# Driver_Morpheus_PONTE_H.net
KiCad netlist of a schematic drawn in Altium Designer
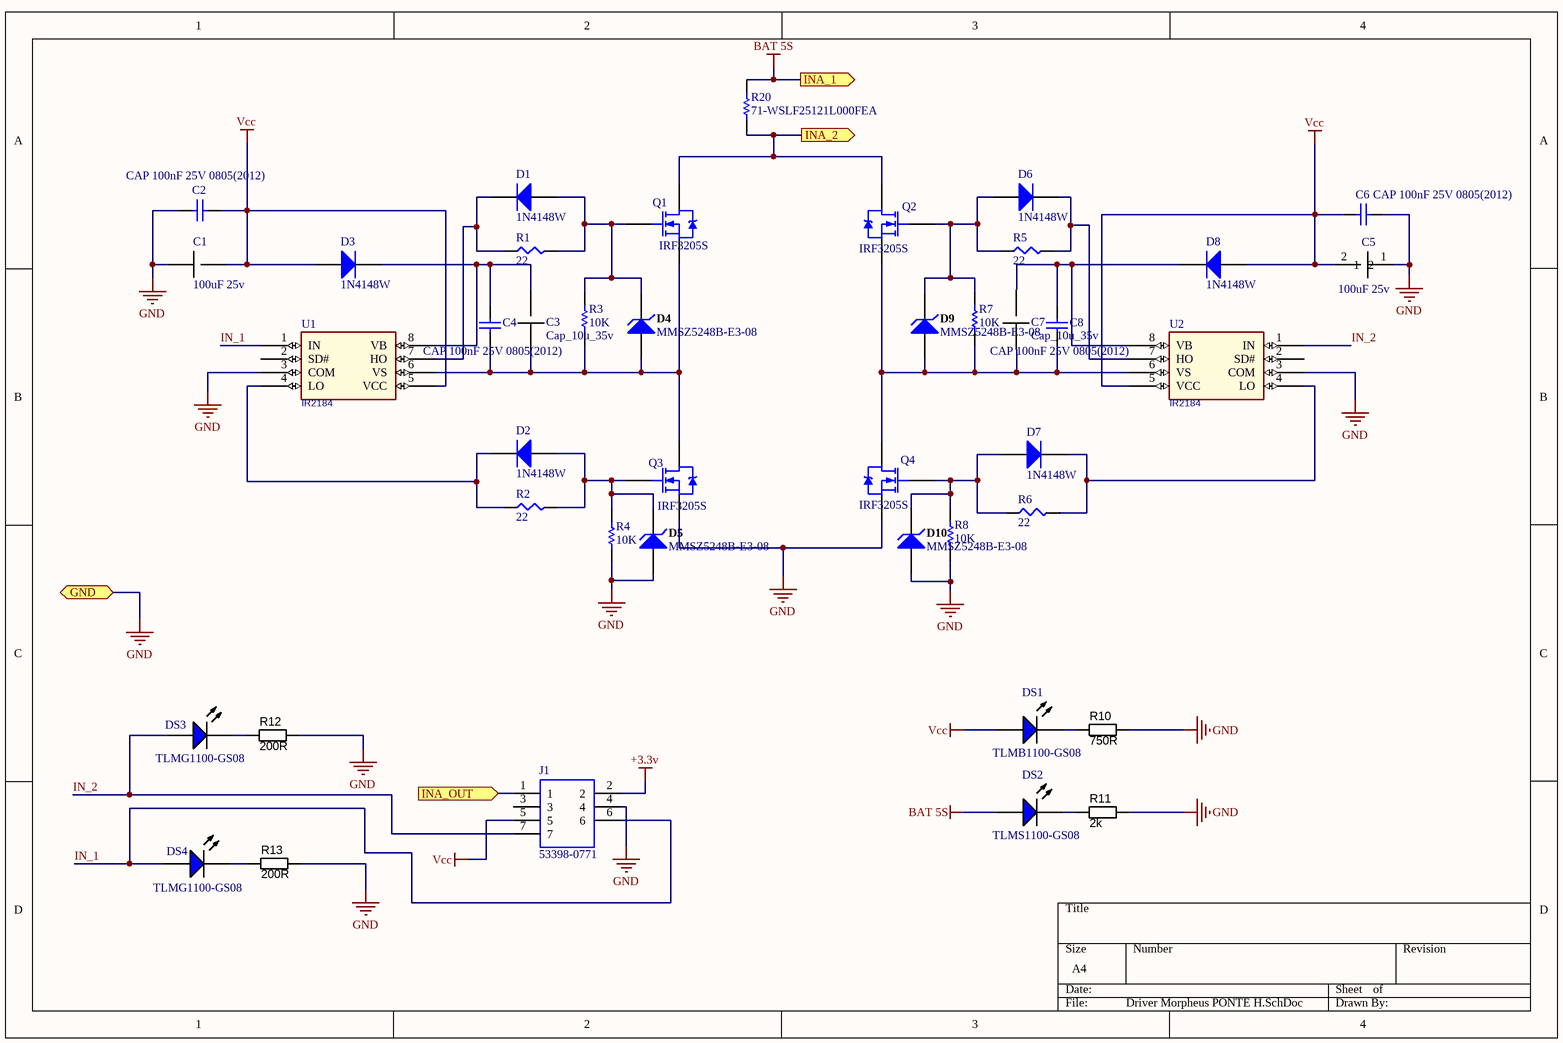
[diagram p0: Driver Morpheus PONTE H.SchDoc]

(export (version "E")
  (design (tool "Eeschema 10.0.6"))
  (components
    (comp (ref "C1")
      (value "100uF 25v")
      (footprint "CAPAE9083X70M")
      (libsource (lib "LibSanhaço2017") (part "Cap_10u_35v"))
    )
    (comp (ref "C2")
      (value "CAP 100nF 25V 0805(2012)")
      (footprint "CAPC0805(2012)145_M")
      (description "CAP 100nF 25V ±5% 0805 (2012 Metric) Thickness 1.45mm SMD")
      (fields (field (name "TOLERANCE") "Â±5%"))
      (libsource (lib "Altium Content Vault") (part "CAP"))
    )
    (comp (ref "C3")
      (value "Cap_10u_35v")
      (footprint "CAP POL 2917/7343")
      (libsource (lib "LibSanhaço2017") (part "Cap_10u_35v"))
    )
    (comp (ref "C4")
      (value "CAP 100nF 25V 0805(2012)")
      (footprint "CAPC0805(2012)145_M")
      (description "CAP 100nF 25V ±5% 0805 (2012 Metric) Thickness 1.45mm SMD")
      (fields (field (name "TOLERANCE") "Â±5%"))
      (libsource (lib "Altium Content Vault") (part "CAP"))
    )
    (comp (ref "C5")
      (value "100uF 25v")
      (footprint "CAPAE9083X70M")
      (description "Cap Tântalo")
      (libsource (lib "LibSanhaço2017") (part "Cap_100u_25v"))
    )
    (comp (ref "C6")
      (value "CAP 100nF 25V 0805(2012)")
      (footprint "CAPC0805(2012)145_M")
      (description "CAP 100nF 25V ±5% 0805 (2012 Metric) Thickness 1.45mm SMD")
      (fields (field (name "TOLERANCE") "Â±5%"))
      (libsource (lib "Altium Content Vault") (part "CAP"))
    )
    (comp (ref "C7")
      (value "Cap_10u_35v")
      (footprint "CAP POL 2917/7343")
      (libsource (lib "LibSanhaço2017") (part "Cap_10u_35v"))
    )
    (comp (ref "C8")
      (value "CAP 100nF 25V 0805(2012)")
      (footprint "CAPC0805(2012)145_M")
      (description "CAP 100nF 25V ±5% 0805 (2012 Metric) Thickness 1.45mm SMD")
      (fields (field (name "TOLERANCE") "Â±5%"))
      (libsource (lib "Altium Content Vault") (part "CAP"))
    )
    (comp (ref "D1")
      (value "1N4148W")
      (footprint "JSCJ-SOD-123-2_V")
      (description "Fast Switching Diode, 75 V, 150 mA, 2-Pin 2.7 x 1.6 x 1.25 mm SMD, Tape and Reel")
      (fields (field (name "MANUFACTURER") "Changjiang Electronics"))
      (libsource (lib "Altium Content Vault") (part "JSCJ-A1K2-2"))
    )
    (comp (ref "D2")
      (value "1N4148W")
      (footprint "JSCJ-SOD-123-2_V")
      (description "Fast Switching Diode, 75 V, 150 mA, 2-Pin 2.7 x 1.6 x 1.25 mm SMD, Tape and Reel")
      (fields (field (name "MANUFACTURER") "Changjiang Electronics"))
      (libsource (lib "Altium Content Vault") (part "JSCJ-A1K2-2"))
    )
    (comp (ref "D3")
      (value "1N4148W")
      (footprint "JSCJ-SOD-123-2_V")
      (description "Fast Switching Diode, 75 V, 150 mA, 2-Pin 2.7 x 1.6 x 1.25 mm SMD, Tape and Reel")
      (fields (field (name "MANUFACTURER") "Changjiang Electronics"))
      (libsource (lib "Altium Content Vault") (part "JSCJ-A1K2-2"))
    )
    (comp (ref "D4")
      (value "MMSZ5248B-E3-08")
      (footprint "VISH-SOD-123-2_V")
      (description "Small Signal Zener Diode, 18 V +/- 5%, -55 to 155 degC, 2-Pin SOD-123, RoHS, Tape and Reel")
      (fields (field (name "TOLERANCE") "+/- 5%") (field (name "MANUFACTURER") "Vishay Semiconductor"))
      (libsource (lib "Altium Content Vault") (part "VISH-DZEN_A1K2-2"))
    )
    (comp (ref "D5")
      (value "MMSZ5248B-E3-08")
      (footprint "VISH-SOD-123-2_V")
      (description "Small Signal Zener Diode, 18 V +/- 5%, -55 to 155 degC, 2-Pin SOD-123, RoHS, Tape and Reel")
      (fields (field (name "TOLERANCE") "+/- 5%") (field (name "MANUFACTURER") "Vishay Semiconductor"))
      (libsource (lib "Altium Content Vault") (part "VISH-DZEN_A1K2-2"))
    )
    (comp (ref "D6")
      (value "1N4148W")
      (footprint "JSCJ-SOD-123-2_V")
      (description "Fast Switching Diode, 75 V, 150 mA, 2-Pin 2.7 x 1.6 x 1.25 mm SMD, Tape and Reel")
      (fields (field (name "MANUFACTURER") "Changjiang Electronics"))
      (libsource (lib "Altium Content Vault") (part "JSCJ-A1K2-2"))
    )
    (comp (ref "D7")
      (value "1N4148W")
      (footprint "JSCJ-SOD-123-2_V")
      (description "Fast Switching Diode, 75 V, 150 mA, 2-Pin 2.7 x 1.6 x 1.25 mm SMD, Tape and Reel")
      (fields (field (name "MANUFACTURER") "Changjiang Electronics"))
      (libsource (lib "Altium Content Vault") (part "JSCJ-A1K2-2"))
    )
    (comp (ref "D8")
      (value "1N4148W")
      (footprint "JSCJ-SOD-123-2_V")
      (description "Fast Switching Diode, 75 V, 150 mA, 2-Pin 2.7 x 1.6 x 1.25 mm SMD, Tape and Reel")
      (fields (field (name "MANUFACTURER") "Changjiang Electronics"))
      (libsource (lib "Altium Content Vault") (part "JSCJ-A1K2-2"))
    )
    (comp (ref "D9")
      (value "MMSZ5248B-E3-08")
      (footprint "VISH-SOD-123-2_V")
      (description "Small Signal Zener Diode, 18 V +/- 5%, -55 to 155 degC, 2-Pin SOD-123, RoHS, Tape and Reel")
      (fields (field (name "TOLERANCE") "+/- 5%") (field (name "MANUFACTURER") "Vishay Semiconductor"))
      (libsource (lib "Altium Content Vault") (part "VISH-DZEN_A1K2-2"))
    )
    (comp (ref "D10")
      (value "MMSZ5248B-E3-08")
      (footprint "VISH-SOD-123-2_V")
      (description "Small Signal Zener Diode, 18 V +/- 5%, -55 to 155 degC, 2-Pin SOD-123, RoHS, Tape and Reel")
      (fields (field (name "TOLERANCE") "+/- 5%") (field (name "MANUFACTURER") "Vishay Semiconductor"))
      (libsource (lib "Altium Content Vault") (part "VISH-DZEN_A1K2-2"))
    )
    (comp (ref "DS1")
      (value "TLMB1100-GS08")
      (footprint "VISH-TLMX1100-2_V")
      (fields (field (name "TOLERANCE") "10%"))
      (libsource (lib "Altium Content Vault") (part "LED-BLUE-AK-2"))
    )
    (comp (ref "DS2")
      (value "TLMS1100-GS08")
      (footprint "VISH-TLMX1100-2_V")
      (fields (field (name "TOLERANCE") "10%"))
      (libsource (lib "Altium Content Vault") (part "LED-BLUE-AK-2"))
    )
    (comp (ref "DS3")
      (value "TLMG1100-GS08")
      (footprint "VISH-TLMX1100-2_V")
      (fields (field (name "TOLERANCE") "10%"))
      (libsource (lib "Altium Content Vault") (part "LED-BLUE-AK-2"))
    )
    (comp (ref "DS4")
      (value "TLMG1100-GS08")
      (footprint "VISH-TLMX1100-2_V")
      (fields (field (name "TOLERANCE") "10%"))
      (libsource (lib "Altium Content Vault") (part "LED-BLUE-AK-2"))
    )
    (comp (ref "J1")
      (value "53398-0771")
      (footprint "53398-0771")
      (fields (field (name "RS PART NUMBER") "5427220P"))
      (libsource (lib "53398-0771") (part "53398-0771"))
    )
    (comp (ref "Q1")
      (value "IRF3205S")
      (footprint "D2PAK_N")
      (description "HEXFET Power MOSFET")
      (fields (field (name "PUBLISHER") "Altium Limited"))
      (libsource (lib "IR Discrete MOSFET - Power") (part "IRF3205S"))
    )
    (comp (ref "Q2")
      (value "IRF3205S")
      (footprint "D2PAK_N")
      (description "HEXFET Power MOSFET")
      (fields (field (name "PUBLISHER") "Altium Limited"))
      (libsource (lib "IR Discrete MOSFET - Power") (part "IRF3205S"))
    )
    (comp (ref "Q3")
      (value "IRF3205S")
      (footprint "D2PAK_N")
      (description "HEXFET Power MOSFET")
      (fields (field (name "PUBLISHER") "Altium Limited"))
      (libsource (lib "IR Discrete MOSFET - Power") (part "IRF3205S"))
    )
    (comp (ref "Q4")
      (value "IRF3205S")
      (footprint "D2PAK_N")
      (description "HEXFET Power MOSFET")
      (fields (field (name "PUBLISHER") "Altium Limited"))
      (libsource (lib "IR Discrete MOSFET - Power") (part "IRF3205S"))
    )
    (comp (ref "R1")
      (value "22")
      (footprint "SMD-0603-RES")
      (description "RES SMD 22 OHM 1% 1/10W 0603")
      (fields
        (field (name "PART NUMBER") "ERJ-3EKF22R0V")
        (field (name "DIGI-KEY PART NUMBER") "P22.0HCT-ND")
      )
      (libsource (lib "Panasonic_ERJ_0603") (part "ERJ-3EKF22R0V"))
    )
    (comp (ref "R2")
      (value "22")
      (footprint "SMD-0603-RES")
      (description "RES SMD 22 OHM 1% 1/10W 0603")
      (fields
        (field (name "PART NUMBER") "ERJ-3EKF22R0V")
        (field (name "DIGI-KEY PART NUMBER") "P22.0HCT-ND")
      )
      (libsource (lib "Panasonic_ERJ_0603") (part "ERJ-3EKF22R0V"))
    )
    (comp (ref "R3")
      (value "10K")
      (footprint "RES-0402")
      (description "RES SMD 10K OHM 5% 1/16W 0402")
      (fields (field (name "Comment") "RC0402JR-071KL"))
      (libsource (lib "Schlib1") (part "RES 1K 0402"))
    )
    (comp (ref "R4")
      (value "10K")
      (footprint "RES-0402")
      (description "RES SMD 10K OHM 5% 1/16W 0402")
      (fields (field (name "Comment") "RC0402JR-071KL"))
      (libsource (lib "Schlib1") (part "RES 1K 0402"))
    )
    (comp (ref "R5")
      (value "22")
      (footprint "SMD-0603-RES")
      (description "RES SMD 22 OHM 1% 1/10W 0603")
      (fields
        (field (name "PART NUMBER") "ERJ-3EKF22R0V")
        (field (name "DIGI-KEY PART NUMBER") "P22.0HCT-ND")
      )
      (libsource (lib "Panasonic_ERJ_0603") (part "ERJ-3EKF22R0V"))
    )
    (comp (ref "R6")
      (value "22")
      (footprint "SMD-0603-RES")
      (description "RES SMD 22 OHM 1% 1/10W 0603")
      (fields
        (field (name "PART NUMBER") "ERJ-3EKF22R0V")
        (field (name "DIGI-KEY PART NUMBER") "P22.0HCT-ND")
      )
      (libsource (lib "Panasonic_ERJ_0603") (part "ERJ-3EKF22R0V"))
    )
    (comp (ref "R7")
      (value "10K")
      (footprint "RES-0402")
      (description "RES SMD 10K OHM 5% 1/16W 0402")
      (fields (field (name "Comment") "RC0402JR-071KL"))
      (libsource (lib "Schlib1") (part "RES 1K 0402"))
    )
    (comp (ref "R8")
      (value "10K")
      (footprint "RES-0402")
      (description "RES SMD 10K OHM 5% 1/16W 0402")
      (fields (field (name "Comment") "RC0402JR-071KL"))
      (libsource (lib "Schlib1") (part "RES 1K 0402"))
    )
    (comp (ref "R10")
      (value "750R")
      (footprint "RESC1608X55N")
      (description "Resistor SMD chip 750 Ohm 1/16W 5% 0603")
      (fields (field (name "TOLERANCE") "±5%") (field (name "Comment") "Thick Film"))
      (libsource (lib "PBL - Resistors") (part "RES_220R_0603_5%"))
    )
    (comp (ref "R11")
      (value "2k")
      (footprint "RESC1608X55N")
      (description "Resistor SMD chip 2k Ohm 1/16W 5% 0603")
      (fields (field (name "TOLERANCE") "±5%") (field (name "Comment") "Thick Film"))
      (libsource (lib "PBL - Resistors") (part "RES_220R_0603_5%"))
    )
    (comp (ref "R12")
      (value "200R")
      (footprint "RESC1608X55N")
      (description "Resistor SMD chip 200 Ohm 1/16W 5% 0603")
      (fields (field (name "TOLERANCE") "±5%") (field (name "Comment") "Thick Film"))
      (libsource (lib "PBL - Resistors") (part "RES_220R_0603_5%"))
    )
    (comp (ref "R13")
      (value "200R")
      (footprint "RESC1608X55N")
      (description "Resistor SMD chip 200 Ohm 1/16W 5% 0603")
      (fields (field (name "TOLERANCE") "±5%") (field (name "Comment") "Thick Film"))
      (libsource (lib "PBL - Resistors") (part "RES_220R_0603_5%"))
    )
    (comp (ref "R20")
      (value "71-WSLF25121L000FEA")
      (footprint "RESC6432X89X76ML25T25")
      (fields (field (name "MANUFACTURER") "Vishay") (field (name "TOLERANCE") "1%"))
      (libsource (lib "Resistor 2512 1m") (part "CMP-2000-07419-1"))
    )
    (comp (ref "U1") (value "IR2184") (libsource (lib "") (part "IR2184_1")))
    (comp (ref "U2") (value "IR2184") (libsource (lib "IR2184_Library") (part "IR2184")))
  )
  (nets
    (net (code "1") (name "+3.3v") (class "Default")
      (node (ref "J1") (pin "2") (pinfunction "2_2") (pintype "passive"))
    )
    (net (code "2") (name "/INA_2") (class "Default")
      (node (ref "Q1") (pin "2") (pinfunction "D_2") (pintype "passive"))
      (node (ref "Q2") (pin "2") (pinfunction "D_2") (pintype "passive"))
      (node (ref "R20") (pin "1") (pinfunction "1_1") (pintype "passive"))
    )
    (net (code "3") (name "/INA_OUT") (class "Default")
      (node (ref "J1") (pin "1") (pinfunction "1_1") (pintype "passive"))
    )
    (net (code "4") (name "/IN_1") (class "Default")
      (node (ref "DS4") (pin "1") (pinfunction "A_1") (pintype "passive"))
      (node (ref "J1") (pin "6") (pinfunction "6_6") (pintype "passive"))
      (node (ref "U1") (pin "1") (pinfunction "IN_1") (pintype "bidirectional"))
    )
    (net (code "5") (name "/IN_2") (class "Default")
      (node (ref "DS3") (pin "1") (pinfunction "A_1") (pintype "passive"))
      (node (ref "J1") (pin "7") (pinfunction "7_7") (pintype "passive"))
      (node (ref "U2") (pin "1") (pinfunction "IN_1") (pintype "bidirectional"))
    )
    (net (code "6") (name "BAT 5S") (class "Default")
      (node (ref "DS2") (pin "1") (pinfunction "A_1") (pintype "passive"))
      (node (ref "R20") (pin "2") (pinfunction "2_2") (pintype "passive"))
    )
    (net (code "7") (name "GND") (class "Default")
      (node (ref "C1") (pin "1") (pinfunction "1_1") (pintype "passive"))
      (node (ref "C2") (pin "1") (pinfunction "1_1") (pintype "passive"))
      (node (ref "C5") (pin "1") (pinfunction "1_1") (pintype "passive"))
      (node (ref "C6") (pin "1") (pinfunction "1_1") (pintype "passive"))
      (node (ref "D10") (pin "1") (pinfunction "A_1") (pintype "passive"))
      (node (ref "D5") (pin "1") (pinfunction "A_1") (pintype "passive"))
      (node (ref "J1") (pin "4") (pinfunction "4_4") (pintype "passive"))
      (node (ref "Q3") (pin "3") (pinfunction "S_3") (pintype "passive"))
      (node (ref "Q4") (pin "3") (pinfunction "S_3") (pintype "passive"))
      (node (ref "R10") (pin "2") (pinfunction "2_2") (pintype "passive"))
      (node (ref "R11") (pin "2") (pinfunction "2_2") (pintype "passive"))
      (node (ref "R12") (pin "2") (pinfunction "2_2") (pintype "passive"))
      (node (ref "R13") (pin "2") (pinfunction "2_2") (pintype "passive"))
      (node (ref "R4") (pin "1") (pinfunction "1_1") (pintype "passive"))
      (node (ref "R8") (pin "1") (pinfunction "1_1") (pintype "passive"))
      (node (ref "U1") (pin "3") (pinfunction "COM_3") (pintype "bidirectional"))
      (node (ref "U2") (pin "3") (pinfunction "COM_3") (pintype "bidirectional"))
    )
    (net (code "8") (name "Net-(D1-+)") (class "Default")
      (node (ref "D1") (pin "1") (pinfunction "+_1") (pintype "passive"))
      (node (ref "D4") (pin "2") (pinfunction "K_2") (pintype "passive"))
      (node (ref "Q1") (pin "1") (pinfunction "G_1") (pintype "passive"))
      (node (ref "R1") (pin "2") (pinfunction "2_2") (pintype "passive"))
      (node (ref "R3") (pin "2") (pinfunction "2_2") (pintype "passive"))
    )
    (net (code "9") (name "Net-(D1--)") (class "Default")
      (node (ref "D1") (pin "2") (pinfunction "-_2") (pintype "passive"))
      (node (ref "R1") (pin "1") (pinfunction "1_1") (pintype "passive"))
      (node (ref "U1") (pin "7") (pinfunction "HO_7") (pintype "bidirectional"))
    )
    (net (code "10") (name "Net-(D2-+)") (class "Default")
      (node (ref "D2") (pin "1") (pinfunction "+_1") (pintype "passive"))
      (node (ref "D5") (pin "2") (pinfunction "K_2") (pintype "passive"))
      (node (ref "Q3") (pin "1") (pinfunction "G_1") (pintype "passive"))
      (node (ref "R2") (pin "2") (pinfunction "2_2") (pintype "passive"))
      (node (ref "R4") (pin "2") (pinfunction "2_2") (pintype "passive"))
    )
    (net (code "11") (name "Net-(D2--)") (class "Default")
      (node (ref "D2") (pin "2") (pinfunction "-_2") (pintype "passive"))
      (node (ref "R2") (pin "1") (pinfunction "1_1") (pintype "passive"))
      (node (ref "U1") (pin "4") (pinfunction "LO_4") (pintype "bidirectional"))
    )
    (net (code "12") (name "Net-(D3--)") (class "Default")
      (node (ref "C3") (pin "2") (pinfunction "2_2") (pintype "passive"))
      (node (ref "C4") (pin "2") (pinfunction "2_2") (pintype "passive"))
      (node (ref "D3") (pin "2") (pinfunction "-_2") (pintype "passive"))
      (node (ref "U1") (pin "8") (pinfunction "VB_8") (pintype "bidirectional"))
    )
    (net (code "13") (name "Net-(D4-A)") (class "Default")
      (node (ref "C3") (pin "1") (pinfunction "1_1") (pintype "passive"))
      (node (ref "C4") (pin "1") (pinfunction "1_1") (pintype "passive"))
      (node (ref "D4") (pin "1") (pinfunction "A_1") (pintype "passive"))
      (node (ref "Q1") (pin "3") (pinfunction "S_3") (pintype "passive"))
      (node (ref "Q3") (pin "2") (pinfunction "D_2") (pintype "passive"))
      (node (ref "R3") (pin "1") (pinfunction "1_1") (pintype "passive"))
      (node (ref "U1") (pin "6") (pinfunction "VS_6") (pintype "bidirectional"))
    )
    (net (code "14") (name "Net-(D6-+)") (class "Default")
      (node (ref "D6") (pin "1") (pinfunction "+_1") (pintype "passive"))
      (node (ref "D9") (pin "2") (pinfunction "K_2") (pintype "passive"))
      (node (ref "Q2") (pin "1") (pinfunction "G_1") (pintype "passive"))
      (node (ref "R5") (pin "1") (pinfunction "1_1") (pintype "passive"))
      (node (ref "R7") (pin "2") (pinfunction "2_2") (pintype "passive"))
    )
    (net (code "15") (name "Net-(D6--)") (class "Default")
      (node (ref "D6") (pin "2") (pinfunction "-_2") (pintype "passive"))
      (node (ref "R5") (pin "2") (pinfunction "2_2") (pintype "passive"))
      (node (ref "U2") (pin "7") (pinfunction "HO_7") (pintype "bidirectional"))
    )
    (net (code "16") (name "Net-(D7--)") (class "Default")
      (node (ref "D7") (pin "2") (pinfunction "-_2") (pintype "passive"))
      (node (ref "R6") (pin "2") (pinfunction "2_2") (pintype "passive"))
      (node (ref "U2") (pin "4") (pinfunction "LO_4") (pintype "bidirectional"))
    )
    (net (code "17") (name "Net-(D8--)") (class "Default")
      (node (ref "C7") (pin "2") (pinfunction "2_2") (pintype "passive"))
      (node (ref "C8") (pin "2") (pinfunction "2_2") (pintype "passive"))
      (node (ref "D8") (pin "2") (pinfunction "-_2") (pintype "passive"))
      (node (ref "U2") (pin "8") (pinfunction "VB_8") (pintype "bidirectional"))
    )
    (net (code "18") (name "Net-(D9-A)") (class "Default")
      (node (ref "C7") (pin "1") (pinfunction "1_1") (pintype "passive"))
      (node (ref "C8") (pin "1") (pinfunction "1_1") (pintype "passive"))
      (node (ref "D9") (pin "1") (pinfunction "A_1") (pintype "passive"))
      (node (ref "Q2") (pin "3") (pinfunction "S_3") (pintype "passive"))
      (node (ref "Q4") (pin "2") (pinfunction "D_2") (pintype "passive"))
      (node (ref "R7") (pin "1") (pinfunction "1_1") (pintype "passive"))
      (node (ref "U2") (pin "6") (pinfunction "VS_6") (pintype "bidirectional"))
    )
    (net (code "19") (name "Net-(D10-K)") (class "Default")
      (node (ref "D10") (pin "2") (pinfunction "K_2") (pintype "passive"))
      (node (ref "D7") (pin "1") (pinfunction "+_1") (pintype "passive"))
      (node (ref "Q4") (pin "1") (pinfunction "G_1") (pintype "passive"))
      (node (ref "R6") (pin "1") (pinfunction "1_1") (pintype "passive"))
      (node (ref "R8") (pin "2") (pinfunction "2_2") (pintype "passive"))
    )
    (net (code "20") (name "Net-(DS1-K)") (class "Default")
      (node (ref "DS1") (pin "2") (pinfunction "K_2") (pintype "passive"))
      (node (ref "R10") (pin "1") (pinfunction "1_1") (pintype "passive"))
    )
    (net (code "21") (name "Net-(DS2-K)") (class "Default")
      (node (ref "DS2") (pin "2") (pinfunction "K_2") (pintype "passive"))
      (node (ref "R11") (pin "1") (pinfunction "1_1") (pintype "passive"))
    )
    (net (code "22") (name "Net-(DS3-K)") (class "Default")
      (node (ref "DS3") (pin "2") (pinfunction "K_2") (pintype "passive"))
      (node (ref "R12") (pin "1") (pinfunction "1_1") (pintype "passive"))
    )
    (net (code "23") (name "Net-(DS4-K)") (class "Default")
      (node (ref "DS4") (pin "2") (pinfunction "K_2") (pintype "passive"))
      (node (ref "R13") (pin "1") (pinfunction "1_1") (pintype "passive"))
    )
    (net (code "24") (name "Vcc") (class "Default")
      (node (ref "C1") (pin "2") (pinfunction "2_2") (pintype "passive"))
      (node (ref "C2") (pin "2") (pinfunction "2_2") (pintype "passive"))
      (node (ref "C5") (pin "2") (pinfunction "2_2") (pintype "passive"))
      (node (ref "C6") (pin "2") (pinfunction "2_2") (pintype "passive"))
      (node (ref "D3") (pin "1") (pinfunction "+_1") (pintype "passive"))
      (node (ref "D8") (pin "1") (pinfunction "+_1") (pintype "passive"))
      (node (ref "DS1") (pin "1") (pinfunction "A_1") (pintype "passive"))
      (node (ref "J1") (pin "5") (pinfunction "5_5") (pintype "passive"))
      (node (ref "U1") (pin "5") (pinfunction "VCC_5") (pintype "bidirectional"))
      (node (ref "U2") (pin "5") (pinfunction "VCC_5") (pintype "bidirectional"))
    )
    (net (code "25") (name "unconnected-(J1-Pad3)") (class "Default")
      (node (ref "J1") (pin "3") (pinfunction "3_3") (pintype "passive"))
    )
    (net (code "26") (name "unconnected-(U1-SD#-Pad2)") (class "Default")
      (node (ref "U1") (pin "2") (pinfunction "SD#_2") (pintype "bidirectional"))
    )
    (net (code "27") (name "unconnected-(U2-SD#-Pad2)") (class "Default")
      (node (ref "U2") (pin "2") (pinfunction "SD#_2") (pintype "bidirectional"))
    )
  )
)
